# SAMC21N_Xplained_Pro_Target_MCU.net
KiCad netlist of a schematic drawn in Altium Designer
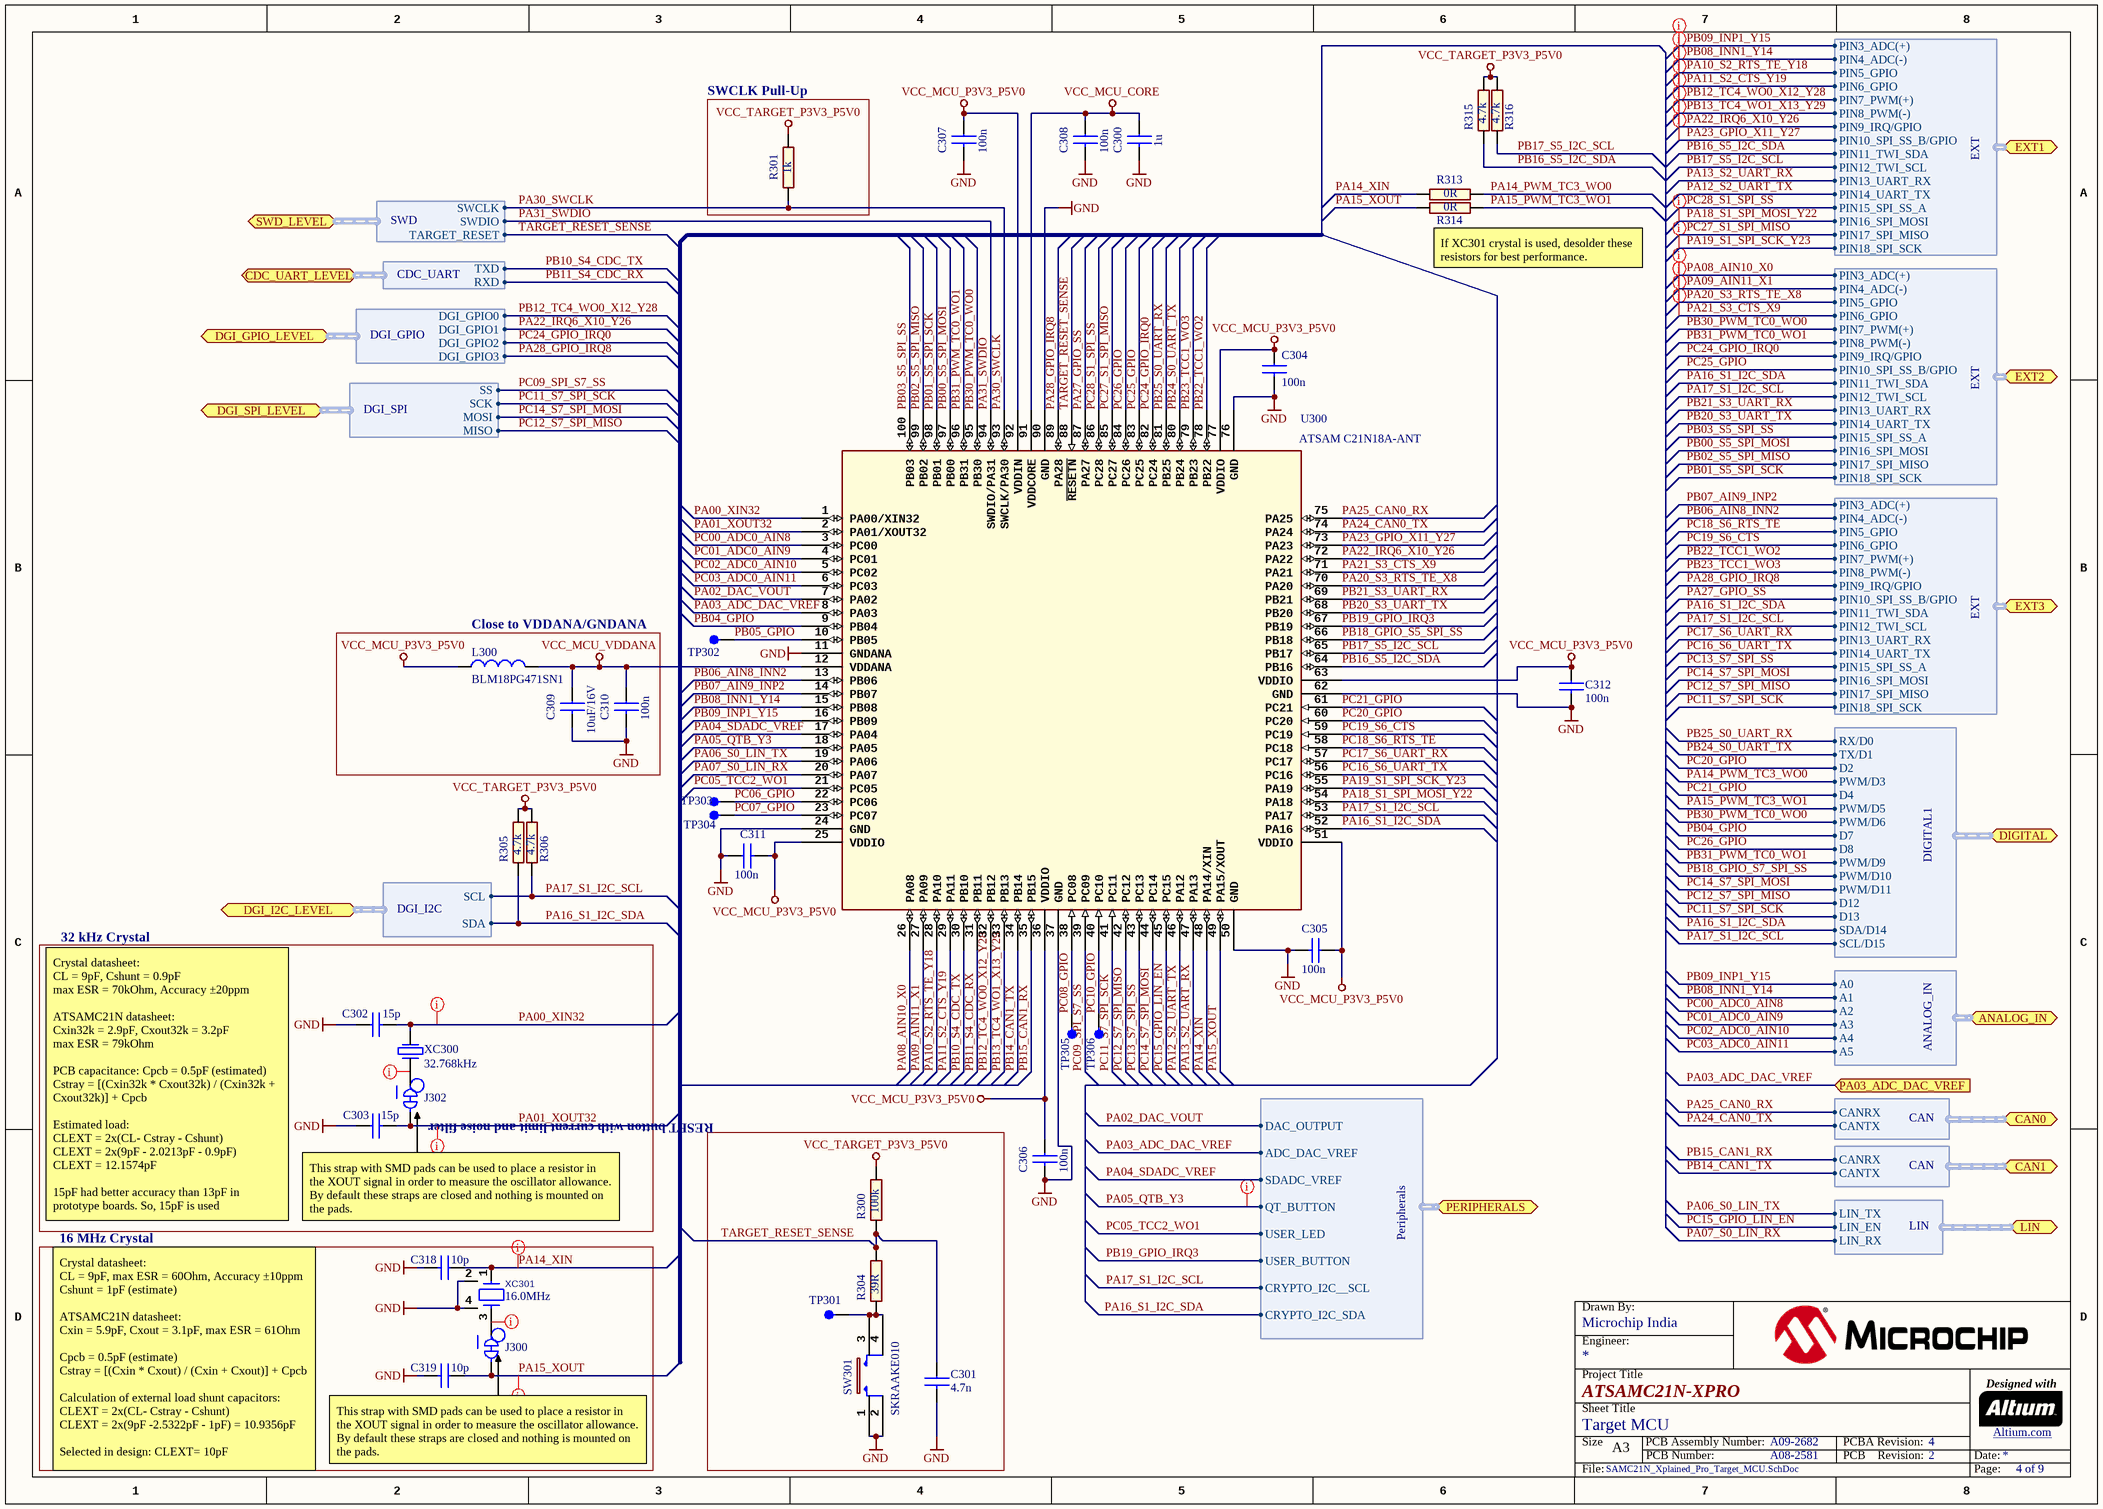
[diagram p0: SAMC21N_Xplained_Pro_Target_MCU.SchDoc]

(export (version "E")
  (design (tool "Eeschema 10.0.6"))
  (components
    (comp (ref "C300")
      (value "1u")
      (footprint "AP1-00001")
      (description "Ceramic capacitor, SMD 0402, X5R, 6.3V, +/-10% (de26942)")
      (fields
        (field (name "TOLERANCE") "+/-10%")
        (field (name "MANUFACTURER") "Kemet")
        (field (name "VERIFIED BY") "Lars Helge Mo")
      )
      (libsource (lib "AltiumDbLib") (part "CAP-NONPOL"))
    )
    (comp (ref "C301")
      (value "4.7n")
      (footprint "AP1-00001")
      (description "Ceramic capacitor, SMD 0402, X7R, 25V, +/-10% (de35287)")
      (fields
        (field (name "TOLERANCE") "25V, +/-10%")
        (field (name "Comment") "CAP-NONPOL")
        (field (name "VERIFIED BY") "Lars Helge Mo")
      )
      (libsource (lib "AltiumDbLib") (part "CAP-NONPOL"))
    )
    (comp (ref "C302")
      (value "15p")
      (footprint "AP1-00001")
      (description "Ceramic capacitor, SMD 0402, NP0, 50V, +/-5%")
      (fields
        (field (name "TOLERANCE") "50V, +/-5%")
        (field (name "MANUFACTURER") "AVX")
        (field (name "VERIFIED BY") "Lars Helge Mo")
      )
      (libsource (lib "AltiumDbLib") (part "CAP-NONPOL"))
    )
    (comp (ref "C303")
      (value "15p")
      (footprint "AP1-00001")
      (description "Ceramic capacitor, SMD 0402, NP0, 50V, +/-5%")
      (fields
        (field (name "TOLERANCE") "50V, +/-5%")
        (field (name "MANUFACTURER") "AVX")
        (field (name "VERIFIED BY") "Lars Helge Mo")
      )
      (libsource (lib "AltiumDbLib") (part "CAP-NONPOL"))
    )
    (comp (ref "C304")
      (value "100n")
      (footprint "AP1-00001")
      (description "Ceramic capacitor, SMD 0402, X7R, 16V, +/-10%")
      (fields
        (field (name "TOLERANCE") "16V, +/-10%")
        (field (name "MANUFACTURER") "Kemet")
        (field (name "VERIFIED BY") "Lars Helge Mo")
      )
      (libsource (lib "AltiumDbLib") (part "CAP-NONPOL"))
    )
    (comp (ref "C305")
      (value "100n")
      (footprint "AP1-00001")
      (description "Ceramic capacitor, SMD 0402, X7R, 16V, +/-10%")
      (fields
        (field (name "TOLERANCE") "16V, +/-10%")
        (field (name "MANUFACTURER") "Kemet")
        (field (name "VERIFIED BY") "Lars Helge Mo")
      )
      (libsource (lib "AltiumDbLib") (part "CAP-NONPOL"))
    )
    (comp (ref "C306")
      (value "100n")
      (footprint "AP1-00001")
      (description "Ceramic capacitor, SMD 0402, X7R, 16V, +/-10%")
      (fields
        (field (name "TOLERANCE") "16V, +/-10%")
        (field (name "MANUFACTURER") "Kemet")
        (field (name "VERIFIED BY") "Lars Helge Mo")
      )
      (libsource (lib "AltiumDbLib") (part "CAP-NONPOL"))
    )
    (comp (ref "C307")
      (value "100n")
      (footprint "AP1-00001")
      (description "Ceramic capacitor, SMD 0402, X7R, 16V, +/-10%")
      (fields
        (field (name "TOLERANCE") "16V, +/-10%")
        (field (name "MANUFACTURER") "Kemet")
        (field (name "VERIFIED BY") "Lars Helge Mo")
      )
      (libsource (lib "AltiumDbLib") (part "CAP-NONPOL"))
    )
    (comp (ref "C308")
      (value "100n")
      (footprint "AP1-00001")
      (description "Ceramic capacitor, SMD 0402, X7R, 16V, +/-10%")
      (fields
        (field (name "TOLERANCE") "16V, +/-10%")
        (field (name "MANUFACTURER") "Kemet")
        (field (name "VERIFIED BY") "Lars Helge Mo")
      )
      (libsource (lib "AltiumDbLib") (part "CAP-NONPOL"))
    )
    (comp (ref "C309")
      (value "10uF/16V")
      (footprint "AP1-00039")
      (description "Ceramic capacitor, SMD 0603, X5R, 16V, 10UF ± 20% (High Density)")
      (fields
        (field (name "MANUFACTURER") "Taiyo Yuden")
        (field (name "MPN") "EMK107BBJ106MA-T")
        (field (name "VERIFIED BY") "Lars Helge Mo")
      )
      (libsource (lib "AltiumDbLib") (part "CAP-NONPOL"))
    )
    (comp (ref "C310")
      (value "100n")
      (footprint "AP1-00001")
      (description "Ceramic capacitor, SMD 0402, X7R, 16V, +/-10%")
      (fields
        (field (name "TOLERANCE") "16V, +/-10%")
        (field (name "MANUFACTURER") "Kemet")
        (field (name "VERIFIED BY") "Lars Helge Mo")
      )
      (libsource (lib "AltiumDbLib") (part "CAP-NONPOL"))
    )
    (comp (ref "C311")
      (value "100n")
      (footprint "AP1-00001")
      (description "Ceramic capacitor, SMD 0402, X7R, 16V, +/-10%")
      (fields
        (field (name "TOLERANCE") "16V, +/-10%")
        (field (name "MANUFACTURER") "Kemet")
        (field (name "VERIFIED BY") "Lars Helge Mo")
      )
      (libsource (lib "AltiumDbLib") (part "CAP-NONPOL"))
    )
    (comp (ref "C312")
      (value "100n")
      (footprint "AP1-00001")
      (description "Ceramic capacitor, SMD 0402, X7R, 16V, +/-10%")
      (fields
        (field (name "TOLERANCE") "16V, +/-10%")
        (field (name "MANUFACTURER") "Kemet")
        (field (name "VERIFIED BY") "Lars Helge Mo")
      )
      (libsource (lib "AltiumDbLib") (part "CAP-NONPOL"))
    )
    (comp (ref "C318")
      (value "10p")
      (footprint "AP1-00001")
      (description "Ceramic capacitor, SMD 0402, NP0, 50V, +/-5%")
      (fields
        (field (name "TOLERANCE") "50V, +/-5%")
        (field (name "Comment") "CAP-NONPOL")
        (field (name "VERIFIED BY") "Lars Helge Mo")
      )
      (libsource (lib "AltiumDbLib") (part "CAP-NONPOL"))
    )
    (comp (ref "C319")
      (value "10p")
      (footprint "AP1-00001")
      (description "Ceramic capacitor, SMD 0402, NP0, 50V, +/-5%")
      (fields
        (field (name "TOLERANCE") "50V, +/-5%")
        (field (name "Comment") "CAP-NONPOL")
        (field (name "VERIFIED BY") "Lars Helge Mo")
      )
      (libsource (lib "AltiumDbLib") (part "CAP-NONPOL"))
    )
    (comp (ref "J300")
      (value "~")
      (footprint "AP9-00044")
      (description "Default closed SMD strap, 0603 size")
      (libsource (lib "AltiumDbLib") (part "SMD-STRAP_CLOSED"))
    )
    (comp (ref "J302")
      (value "~")
      (footprint "AP9-00044")
      (description "Default closed SMD strap, 0603 size")
      (libsource (lib "AltiumDbLib") (part "SMD-STRAP_CLOSED"))
    )
    (comp (ref "L300")
      (value "BLM18PG471SN1")
      (footprint "AP3-00005")
      (description "SMD RF inductor 0603. Z=470Ohm (@100MHz), Max R(dc)=0.65Ohm, Max current=1A")
      (fields
        (field (name "TOLERANCE") "±25%")
        (field (name "MANUFACTURER") "Murata")
        (field (name "VERIFIED BY") "Lars Helge Mo")
      )
      (libsource (lib "AltiumDbLib") (part "INDUCTOR"))
    )
    (comp (ref "R300")
      (value "100k")
      (footprint "AP2-00011")
      (description "Thick film resistor, SMD 0402, 1/16W, 1%")
      (fields
        (field (name "TOLERANCE") "1 %")
        (field (name "Comment") "R2")
        (field (name "VERIFIED BY") "Lars Helge Mo")
      )
      (libsource (lib "AltiumDbLib") (part "R2"))
    )
    (comp (ref "R301")
      (value "1k")
      (footprint "AP2-00000")
      (description "Thick film resistor, SMD 0402, 1/16W, 1%")
      (fields
        (field (name "TOLERANCE") "1 %")
        (field (name "Comment") "R2")
        (field (name "VERIFIED BY") "Lars Helge Mo")
      )
      (libsource (lib "AltiumDbLib") (part "R2"))
    )
    (comp (ref "R304")
      (value "39R")
      (footprint "AP2-00011")
      (description "Thick film resistor, SMD 0402, 1/16W, 1%")
      (fields
        (field (name "TOLERANCE") "1 %")
        (field (name "Comment") "R2")
        (field (name "VERIFIED BY") "Lars Helge Mo")
      )
      (libsource (lib "") (part "R2_2"))
    )
    (comp (ref "R305")
      (value "4.7k")
      (footprint "AP2-00000")
      (description "Thick film resistor, SMD 0402, 1/16W, 1%")
      (fields
        (field (name "TOLERANCE") "1 %")
        (field (name "Comment") "R2")
        (field (name "VERIFIED BY") "Lars Helge Mo")
      )
      (libsource (lib "AltiumDbLib") (part "R2"))
    )
    (comp (ref "R306")
      (value "4.7k")
      (footprint "AP2-00000")
      (description "Thick film resistor, SMD 0402, 1/16W, 1%")
      (fields
        (field (name "TOLERANCE") "1 %")
        (field (name "Comment") "R2")
        (field (name "VERIFIED BY") "Lars Helge Mo")
      )
      (libsource (lib "AltiumDbLib") (part "R2"))
    )
    (comp (ref "R313")
      (value "0R")
      (footprint "AP2-00000")
      (description "Thick film resistor, SMD 0402, 1/16W, 1%")
      (fields
        (field (name "TOLERANCE") "1 %")
        (field (name "Comment") "R2")
        (field (name "VERIFIED BY") "Lars Helge Mo")
      )
      (libsource (lib "") (part "R2_1"))
    )
    (comp (ref "R314")
      (value "0R")
      (footprint "AP2-00000")
      (description "Thick film resistor, SMD 0402, 1/16W, 1%")
      (fields
        (field (name "TOLERANCE") "1 %")
        (field (name "Comment") "R2")
        (field (name "VERIFIED BY") "Lars Helge Mo")
      )
      (libsource (lib "") (part "R2_1"))
    )
    (comp (ref "R315")
      (value "4.7k")
      (footprint "AP2-00000")
      (description "Thick film resistor, SMD 0402, 1/16W, 1%")
      (fields
        (field (name "TOLERANCE") "1 %")
        (field (name "Comment") "R2")
        (field (name "VERIFIED BY") "Lars Helge Mo")
      )
      (libsource (lib "AltiumDbLib") (part "R2"))
    )
    (comp (ref "R316")
      (value "4.7k")
      (footprint "AP2-00000")
      (description "Thick film resistor, SMD 0402, 1/16W, 1%")
      (fields
        (field (name "TOLERANCE") "1 %")
        (field (name "Comment") "R2")
        (field (name "VERIFIED BY") "Lars Helge Mo")
      )
      (libsource (lib "AltiumDbLib") (part "R2"))
    )
    (comp (ref "SW301")
      (value "SKRAAKE010")
      (footprint "AP8-00137")
      (description "6.2x6.2 mm SMD tact switch, same as A08-0091 but less force is needed")
      (fields
        (field (name "MANUFACTURER") "ALPS")
        (field (name "Comment") "Can be ordered in low volumes from Mouser")
        (field (name "VERIFIED BY") "Ketil Skjerve")
      )
      (libsource (lib "AltiumDbLib") (part "PUSHBUTTON1"))
    )
    (comp (ref "TP301")
      (value "TESTPOINT")
      (footprint "AP8-00010")
      (description "Single SMD testpad")
      (fields (field (name "VERIFIED BY") "Sveinung Helgeland"))
      (libsource (lib "AltiumDbLib") (part "TESTPOINT"))
    )
    (comp (ref "TP302")
      (value "TESTPOINT")
      (footprint "AP8-00256")
      (description "Hole for user grid with 1.27 mm pitch, 1x1 mm pad")
      (fields (field (name "VERIFIED BY") "Sveinung Helgeland"))
      (libsource (lib "AltiumDbLib") (part "TESTPOINT"))
    )
    (comp (ref "TP303")
      (value "TESTPOINT")
      (footprint "AP8-00256")
      (description "Hole for user grid with 1.27 mm pitch, 1x1 mm pad")
      (fields (field (name "VERIFIED BY") "Sveinung Helgeland"))
      (libsource (lib "AltiumDbLib") (part "TESTPOINT"))
    )
    (comp (ref "TP304")
      (value "TESTPOINT")
      (footprint "AP8-00256")
      (description "Hole for user grid with 1.27 mm pitch, 1x1 mm pad")
      (fields (field (name "VERIFIED BY") "Sveinung Helgeland"))
      (libsource (lib "AltiumDbLib") (part "TESTPOINT"))
    )
    (comp (ref "TP305")
      (value "TESTPOINT")
      (footprint "AP8-00256")
      (description "Hole for user grid with 1.27 mm pitch, 1x1 mm pad")
      (fields (field (name "VERIFIED BY") "Sveinung Helgeland"))
      (libsource (lib "AltiumDbLib") (part "TESTPOINT"))
    )
    (comp (ref "TP306")
      (value "TESTPOINT")
      (footprint "AP8-00256")
      (description "Hole for user grid with 1.27 mm pitch, 1x1 mm pad")
      (fields (field (name "VERIFIED BY") "Sveinung Helgeland"))
      (libsource (lib "AltiumDbLib") (part "TESTPOINT"))
    )
    (comp (ref "U300")
      (value "ATSAM C21N18A-ANT")
      (footprint "AP6-00008")
      (description "Atmel 32-bit ARM Cortex-M0+ processor 100pin 256KB Flash 32KB SRAM 48MHz freq")
      (fields (field (name "MANUFACTURER") "ATMEL") (field (name "Comment") "SAMC21N_TQFP100"))
      (libsource (lib "AltiumDbLib") (part "SAMC21N_TQFP100"))
    )
    (comp (ref "XC300")
      (value "32.768kHz")
      (footprint "AP7-00090")
      (description "Kyocera ST3215SB32768E0HPWBB, 32.768kHz, 9pF, SMD tuning fork crystal")
      (fields
        (field (name "TOLERANCE") "Â±20ppm")
        (field (name "MANUFACTURER") "Kyocera Crystal Device Corporation")
        (field (name "VERIFIED BY") "Sveinung Helgeland")
      )
      (libsource (lib "AltiumDbLib") (part "CRYSTAL"))
    )
    (comp (ref "XC301")
      (value "16.0MHz")
      (footprint "AP7-00061")
      (description "16MHz uXtal, 3.2 x 2.5 mm SMD, CL=9pF, 15PPM, ESR=80ohm(Max.")
      (fields (field (name "TOLERANCE") "15ppm") (field (name "MANUFACTURER") "Epson Toyocom"))
      (libsource (lib "AltiumDbLib") (part "TSX-3225"))
    )
  )
  (nets
    (net (code "12") (name "/PA00_XIN32") (class "Default")
      (node (ref "C302") (pin "2") (pinfunction "2_2") (pintype "passive"))
      (node (ref "U300") (pin "1") (pinfunction "PA00/XIN32_1") (pintype "bidirectional"))
      (node (ref "XC300") (pin "1") (pinfunction "1_1") (pintype "passive"))
    )
    (net (code "13") (name "/PA01_XOUT32") (class "Default")
      (node (ref "C303") (pin "2") (pinfunction "2_2") (pintype "passive"))
      (node (ref "J302") (pin "2") (pinfunction "2_2") (pintype "passive"))
      (node (ref "U300") (pin "2") (pinfunction "PA01/XOUT32_2") (pintype "bidirectional"))
    )
    (net (code "14") (name "/PA02_DAC_VOUT") (class "Default")
      (node (ref "U300") (pin "7") (pinfunction "PA02_7") (pintype "bidirectional"))
    )
    (net (code "15") (name "/PA03_ADC_DAC_VREF") (class "Default")
      (node (ref "U300") (pin "8") (pinfunction "PA03_8") (pintype "bidirectional"))
    )
    (net (code "16") (name "/PA04_SDADC_VREF") (class "Default")
      (node (ref "U300") (pin "17") (pinfunction "PA04_17") (pintype "bidirectional"))
    )
    (net (code "17") (name "/PA05_QTB_Y3") (class "Default")
      (node (ref "U300") (pin "18") (pinfunction "PA05_18") (pintype "bidirectional"))
    )
    (net (code "18") (name "/PA06_S0_LIN_TX") (class "Default")
      (node (ref "U300") (pin "19") (pinfunction "PA06_19") (pintype "bidirectional"))
    )
    (net (code "19") (name "/PA07_S0_LIN_RX") (class "Default")
      (node (ref "U300") (pin "20") (pinfunction "PA07_20") (pintype "bidirectional"))
    )
    (net (code "20") (name "/PA08_AIN10_X0") (class "Default")
      (node (ref "U300") (pin "26") (pinfunction "PA08_26") (pintype "bidirectional"))
    )
    (net (code "21") (name "/PA09_AIN11_X1") (class "Default")
      (node (ref "U300") (pin "27") (pinfunction "PA09_27") (pintype "bidirectional"))
    )
    (net (code "22") (name "/PA10_S2_RTS_TE_Y18") (class "Default")
      (node (ref "U300") (pin "28") (pinfunction "PA10_28") (pintype "bidirectional"))
    )
    (net (code "23") (name "/PA11_S2_CTS_Y19") (class "Default")
      (node (ref "U300") (pin "29") (pinfunction "PA11_29") (pintype "bidirectional"))
    )
    (net (code "24") (name "/PA12_S2_UART_TX") (class "Default")
      (node (ref "U300") (pin "46") (pinfunction "PA12_46") (pintype "bidirectional"))
    )
    (net (code "25") (name "/PA13_S2_UART_RX") (class "Default")
      (node (ref "U300") (pin "47") (pinfunction "PA13_47") (pintype "bidirectional"))
    )
    (net (code "26") (name "/PA14_PWM_TC3_WO0") (class "Default")
      (node (ref "R313") (pin "2") (pinfunction "2_2") (pintype "passive"))
    )
    (net (code "27") (name "/PA14_XIN") (class "Default")
      (node (ref "C318") (pin "1") (pinfunction "1_1") (pintype "passive"))
      (node (ref "R313") (pin "1") (pinfunction "1_1") (pintype "passive"))
      (node (ref "U300") (pin "48") (pinfunction "PA14/XIN_48") (pintype "bidirectional"))
      (node (ref "XC301") (pin "1") (pinfunction "IN_1") (pintype "passive"))
    )
    (net (code "28") (name "/PA15_PWM_TC3_WO1") (class "Default")
      (node (ref "R314") (pin "2") (pinfunction "2_2") (pintype "passive"))
    )
    (net (code "29") (name "/PA15_XOUT") (class "Default")
      (node (ref "C319") (pin "1") (pinfunction "1_1") (pintype "passive"))
      (node (ref "J300") (pin "2") (pinfunction "2_2") (pintype "passive"))
      (node (ref "R314") (pin "1") (pinfunction "1_1") (pintype "passive"))
      (node (ref "U300") (pin "49") (pinfunction "PA15/XOUT_49") (pintype "bidirectional"))
    )
    (net (code "30") (name "/PA16_S1_I2C_SDA") (class "Default")
      (node (ref "R305") (pin "1") (pinfunction "1_1") (pintype "passive"))
      (node (ref "U300") (pin "52") (pinfunction "PA16_52") (pintype "bidirectional"))
    )
    (net (code "31") (name "/PA17_S1_I2C_SCL") (class "Default")
      (node (ref "R306") (pin "1") (pinfunction "1_1") (pintype "passive"))
      (node (ref "U300") (pin "53") (pinfunction "PA17_53") (pintype "bidirectional"))
    )
    (net (code "32") (name "/PA18_S1_SPI_MOSI_Y22") (class "Default")
      (node (ref "U300") (pin "54") (pinfunction "PA18_54") (pintype "bidirectional"))
    )
    (net (code "33") (name "/PA19_S1_SPI_SCK_Y23") (class "Default")
      (node (ref "U300") (pin "55") (pinfunction "PA19_55") (pintype "bidirectional"))
    )
    (net (code "34") (name "/PA20_S3_RTS_TE_X8") (class "Default")
      (node (ref "U300") (pin "70") (pinfunction "PA20_70") (pintype "bidirectional"))
    )
    (net (code "35") (name "/PA21_S3_CTS_X9") (class "Default")
      (node (ref "U300") (pin "71") (pinfunction "PA21_71") (pintype "bidirectional"))
    )
    (net (code "36") (name "/PA22_IRQ6_X10_Y26") (class "Default")
      (node (ref "U300") (pin "72") (pinfunction "PA22_72") (pintype "bidirectional"))
    )
    (net (code "37") (name "/PA23_GPIO_X11_Y27") (class "Default")
      (node (ref "U300") (pin "73") (pinfunction "PA23_73") (pintype "bidirectional"))
    )
    (net (code "38") (name "/PA24_CAN0_TX") (class "Default")
      (node (ref "U300") (pin "74") (pinfunction "PA24_74") (pintype "bidirectional"))
    )
    (net (code "39") (name "/PA25_CAN0_RX") (class "Default")
      (node (ref "U300") (pin "75") (pinfunction "PA25_75") (pintype "bidirectional"))
    )
    (net (code "40") (name "/PA27_GPIO_SS") (class "Default")
      (node (ref "U300") (pin "87") (pinfunction "PA27_87") (pintype "bidirectional"))
    )
    (net (code "41") (name "/PA28_GPIO_IRQ8") (class "Default")
      (node (ref "U300") (pin "89") (pinfunction "PA28_89") (pintype "bidirectional"))
    )
    (net (code "42") (name "/PA30_SWCLK") (class "Default")
      (node (ref "R301") (pin "1") (pinfunction "1_1") (pintype "passive"))
      (node (ref "U300") (pin "93") (pinfunction "SWCLK/PA30_93") (pintype "bidirectional"))
    )
    (net (code "43") (name "/PA31_SWDIO") (class "Default")
      (node (ref "U300") (pin "94") (pinfunction "SWDIO/PA31_94") (pintype "bidirectional"))
    )
    (net (code "44") (name "/PB00_S5_SPI_MOSI") (class "Default")
      (node (ref "U300") (pin "97") (pinfunction "PB00_97") (pintype "bidirectional"))
    )
    (net (code "45") (name "/PB01_S5_SPI_SCK") (class "Default")
      (node (ref "U300") (pin "98") (pinfunction "PB01_98") (pintype "bidirectional"))
    )
    (net (code "46") (name "/PB02_S5_SPI_MISO") (class "Default")
      (node (ref "U300") (pin "99") (pinfunction "PB02_99") (pintype "bidirectional"))
    )
    (net (code "47") (name "/PB03_S5_SPI_SS") (class "Default")
      (node (ref "U300") (pin "100") (pinfunction "PB03_100") (pintype "bidirectional"))
    )
    (net (code "48") (name "/PB04_GPIO") (class "Default")
      (node (ref "U300") (pin "9") (pinfunction "PB04_9") (pintype "bidirectional"))
    )
    (net (code "49") (name "/PB05_GPIO") (class "Default")
      (node (ref "TP302") (pin "1") (pinfunction "1_1") (pintype "passive"))
      (node (ref "U300") (pin "10") (pinfunction "PB05_10") (pintype "bidirectional"))
    )
    (net (code "50") (name "/PB06_AIN8_INN2") (class "Default")
      (node (ref "U300") (pin "13") (pinfunction "PB06_13") (pintype "bidirectional"))
    )
    (net (code "51") (name "/PB07_AIN9_INP2") (class "Default")
      (node (ref "U300") (pin "14") (pinfunction "PB07_14") (pintype "bidirectional"))
    )
    (net (code "52") (name "/PB08_INN1_Y14") (class "Default")
      (node (ref "U300") (pin "15") (pinfunction "PB08_15") (pintype "bidirectional"))
    )
    (net (code "53") (name "/PB09_INP1_Y15") (class "Default")
      (node (ref "U300") (pin "16") (pinfunction "PB09_16") (pintype "bidirectional"))
    )
    (net (code "54") (name "/PB10_S4_CDC_TX") (class "Default")
      (node (ref "U300") (pin "30") (pinfunction "PB10_30") (pintype "bidirectional"))
    )
    (net (code "55") (name "/PB11_S4_CDC_RX") (class "Default")
      (node (ref "U300") (pin "31") (pinfunction "PB11_31") (pintype "bidirectional"))
    )
    (net (code "56") (name "/PB12_TC4_WO0_X12_Y28") (class "Default")
      (node (ref "U300") (pin "32") (pinfunction "PB12_32") (pintype "bidirectional"))
    )
    (net (code "57") (name "/PB13_TC4_WO1_X13_Y29") (class "Default")
      (node (ref "U300") (pin "33") (pinfunction "PB13_33") (pintype "bidirectional"))
    )
    (net (code "58") (name "/PB14_CAN1_TX") (class "Default")
      (node (ref "U300") (pin "34") (pinfunction "PB14_34") (pintype "bidirectional"))
    )
    (net (code "59") (name "/PB15_CAN1_RX") (class "Default")
      (node (ref "U300") (pin "35") (pinfunction "PB15_35") (pintype "bidirectional"))
    )
    (net (code "60") (name "/PB16_S5_I2C_SDA") (class "Default")
      (node (ref "R315") (pin "1") (pinfunction "1_1") (pintype "passive"))
      (node (ref "U300") (pin "64") (pinfunction "PB16_64") (pintype "bidirectional"))
    )
    (net (code "61") (name "/PB17_S5_I2C_SCL") (class "Default")
      (node (ref "R316") (pin "1") (pinfunction "1_1") (pintype "passive"))
      (node (ref "U300") (pin "65") (pinfunction "PB17_65") (pintype "bidirectional"))
    )
    (net (code "62") (name "/PB18_GPIO_S5_SPI_SS") (class "Default")
      (node (ref "U300") (pin "66") (pinfunction "PB18_66") (pintype "bidirectional"))
    )
    (net (code "64") (name "/PB19_GPIO_IRQ3") (class "Default")
      (node (ref "U300") (pin "67") (pinfunction "PB19_67") (pintype "bidirectional"))
    )
    (net (code "65") (name "/PB20_S3_UART_TX") (class "Default")
      (node (ref "U300") (pin "68") (pinfunction "PB20_68") (pintype "bidirectional"))
    )
    (net (code "66") (name "/PB21_S3_UART_RX") (class "Default")
      (node (ref "U300") (pin "69") (pinfunction "PB21_69") (pintype "bidirectional"))
    )
    (net (code "67") (name "/PB22_TCC1_WO2") (class "Default")
      (node (ref "U300") (pin "78") (pinfunction "PB22_78") (pintype "bidirectional"))
    )
    (net (code "68") (name "/PB23_TCC1_WO3") (class "Default")
      (node (ref "U300") (pin "79") (pinfunction "PB23_79") (pintype "bidirectional"))
    )
    (net (code "69") (name "/PB24_S0_UART_TX") (class "Default")
      (node (ref "U300") (pin "80") (pinfunction "PB24_80") (pintype "bidirectional"))
    )
    (net (code "70") (name "/PB25_S0_UART_RX") (class "Default")
      (node (ref "U300") (pin "81") (pinfunction "PB25_81") (pintype "bidirectional"))
    )
    (net (code "71") (name "/PB30_PWM_TC0_WO0") (class "Default")
      (node (ref "U300") (pin "95") (pinfunction "PB30_95") (pintype "bidirectional"))
    )
    (net (code "72") (name "/PB31_PWM_TC0_WO1") (class "Default")
      (node (ref "U300") (pin "96") (pinfunction "PB31_96") (pintype "bidirectional"))
    )
    (net (code "73") (name "/PC00_ADC0_AIN8") (class "Default")
      (node (ref "U300") (pin "3") (pinfunction "PC00_3") (pintype "bidirectional"))
    )
    (net (code "74") (name "/PC01_ADC0_AIN9") (class "Default")
      (node (ref "U300") (pin "4") (pinfunction "PC01_4") (pintype "bidirectional"))
    )
    (net (code "75") (name "/PC02_ADC0_AIN10") (class "Default")
      (node (ref "U300") (pin "5") (pinfunction "PC02_5") (pintype "bidirectional"))
    )
    (net (code "76") (name "/PC03_ADC0_AIN11") (class "Default")
      (node (ref "U300") (pin "6") (pinfunction "PC03_6") (pintype "bidirectional"))
    )
    (net (code "77") (name "/PC05_TCC2_WO1") (class "Default")
      (node (ref "U300") (pin "21") (pinfunction "PC05_21") (pintype "bidirectional"))
    )
    (net (code "78") (name "/PC06_GPIO") (class "Default")
      (node (ref "TP303") (pin "1") (pinfunction "1_1") (pintype "passive"))
      (node (ref "U300") (pin "22") (pinfunction "PC06_22") (pintype "bidirectional"))
    )
    (net (code "79") (name "/PC07_GPIO") (class "Default")
      (node (ref "TP304") (pin "1") (pinfunction "1_1") (pintype "passive"))
      (node (ref "U300") (pin "23") (pinfunction "PC07_23") (pintype "bidirectional"))
    )
    (net (code "80") (name "/PC08_GPIO") (class "Default")
      (node (ref "TP305") (pin "1") (pinfunction "1_1") (pintype "passive"))
      (node (ref "U300") (pin "38") (pinfunction "PC08_38") (pintype "input"))
    )
    (net (code "81") (name "/PC09_SPI_S7_SS") (class "Default")
      (node (ref "U300") (pin "39") (pinfunction "PC09_39") (pintype "input"))
    )
    (net (code "82") (name "/PC10_GPIO") (class "Default")
      (node (ref "TP306") (pin "1") (pinfunction "1_1") (pintype "passive"))
      (node (ref "U300") (pin "40") (pinfunction "PC10_40") (pintype "input"))
    )
    (net (code "83") (name "/PC11_S7_SPI_SCK") (class "Default")
      (node (ref "U300") (pin "41") (pinfunction "PC11_41") (pintype "input"))
    )
    (net (code "84") (name "/PC12_S7_SPI_MISO") (class "Default")
      (node (ref "U300") (pin "42") (pinfunction "PC12_42") (pintype "bidirectional"))
    )
    (net (code "85") (name "/PC13_S7_SPI_SS") (class "Default")
      (node (ref "U300") (pin "43") (pinfunction "PC13_43") (pintype "bidirectional"))
    )
    (net (code "86") (name "/PC14_S7_SPI_MOSI") (class "Default")
      (node (ref "U300") (pin "44") (pinfunction "PC14_44") (pintype "bidirectional"))
    )
    (net (code "87") (name "/PC15_GPIO_LIN_EN") (class "Default")
      (node (ref "U300") (pin "45") (pinfunction "PC15_45") (pintype "bidirectional"))
    )
    (net (code "88") (name "/PC16_S6_UART_TX") (class "Default")
      (node (ref "U300") (pin "56") (pinfunction "PC16_56") (pintype "bidirectional"))
    )
    (net (code "89") (name "/PC17_S6_UART_RX") (class "Default")
      (node (ref "U300") (pin "57") (pinfunction "PC17_57") (pintype "bidirectional"))
    )
    (net (code "90") (name "/PC18_S6_RTS_TE") (class "Default")
      (node (ref "U300") (pin "58") (pinfunction "PC18_58") (pintype "input"))
    )
    (net (code "91") (name "/PC19_S6_CTS") (class "Default")
      (node (ref "U300") (pin "59") (pinfunction "PC19_59") (pintype "input"))
    )
    (net (code "92") (name "/PC20_GPIO") (class "Default")
      (node (ref "U300") (pin "60") (pinfunction "PC20_60") (pintype "input"))
    )
    (net (code "93") (name "/PC21_GPIO") (class "Default")
      (node (ref "U300") (pin "61") (pinfunction "PC21_61") (pintype "input"))
    )
    (net (code "94") (name "/PC24_GPIO_IRQ0") (class "Default")
      (node (ref "U300") (pin "82") (pinfunction "PC24_82") (pintype "bidirectional"))
    )
    (net (code "95") (name "/PC25_GPIO") (class "Default")
      (node (ref "U300") (pin "83") (pinfunction "PC25_83") (pintype "bidirectional"))
    )
    (net (code "96") (name "/PC26_GPIO") (class "Default")
      (node (ref "U300") (pin "84") (pinfunction "PC26_84") (pintype "bidirectional"))
    )
    (net (code "97") (name "/PC27_S1_SPI_MISO") (class "Default")
      (node (ref "U300") (pin "85") (pinfunction "PC27_85") (pintype "bidirectional"))
    )
    (net (code "98") (name "/PC28_S1_SPI_SS") (class "Default")
      (node (ref "U300") (pin "86") (pinfunction "PC28_86") (pintype "bidirectional"))
    )
    (net (code "99") (name "/TARGET_RESET_SENSE") (class "Default")
      (node (ref "C301") (pin "1") (pinfunction "1_1") (pintype "passive"))
      (node (ref "R300") (pin "1") (pinfunction "1_1") (pintype "passive"))
      (node (ref "R304") (pin "2") (pinfunction "2_2") (pintype "passive"))
      (node (ref "U300") (pin "88") (pinfunction "~{RESETN}_88") (pintype "input"))
    )
    (net (code "111") (name "GND") (class "Default")
      (node (ref "C300") (pin "2") (pinfunction "2_2") (pintype "passive"))
      (node (ref "C301") (pin "2") (pinfunction "2_2") (pintype "passive"))
      (node (ref "C302") (pin "1") (pinfunction "1_1") (pintype "passive"))
      (node (ref "C303") (pin "1") (pinfunction "1_1") (pintype "passive"))
      (node (ref "C304") (pin "2") (pinfunction "2_2") (pintype "passive"))
      (node (ref "C305") (pin "2") (pinfunction "2_2") (pintype "passive"))
      (node (ref "C306") (pin "2") (pinfunction "2_2") (pintype "passive"))
      (node (ref "C307") (pin "2") (pinfunction "2_2") (pintype "passive"))
      (node (ref "C308") (pin "2") (pinfunction "2_2") (pintype "passive"))
      (node (ref "C309") (pin "2") (pinfunction "2_2") (pintype "passive"))
      (node (ref "C310") (pin "2") (pinfunction "2_2") (pintype "passive"))
      (node (ref "C311") (pin "1") (pinfunction "1_1") (pintype "passive"))
      (node (ref "C312") (pin "2") (pinfunction "2_2") (pintype "passive"))
      (node (ref "C318") (pin "2") (pinfunction "2_2") (pintype "passive"))
      (node (ref "C319") (pin "2") (pinfunction "2_2") (pintype "passive"))
      (node (ref "SW301") (pin "1") (pinfunction "1_1") (pintype "passive"))
      (node (ref "SW301") (pin "2") (pinfunction "2_2") (pintype "passive"))
      (node (ref "U300") (pin "11") (pinfunction "GNDANA_11") (pintype "power_in"))
      (node (ref "U300") (pin "24") (pinfunction "GND_24") (pintype "power_in"))
      (node (ref "U300") (pin "37") (pinfunction "GND_37") (pintype "power_in"))
      (node (ref "U300") (pin "50") (pinfunction "GND_50") (pintype "power_in"))
      (node (ref "U300") (pin "62") (pinfunction "GND_62") (pintype "power_in"))
      (node (ref "U300") (pin "76") (pinfunction "GND_76") (pintype "power_in"))
      (node (ref "U300") (pin "90") (pinfunction "GND_90") (pintype "power_in"))
      (node (ref "XC301") (pin "2") (pinfunction "GND_2") (pintype "passive"))
      (node (ref "XC301") (pin "4") (pinfunction "GND_4") (pintype "passive"))
    )
    (net (code "112") (name "Net-(J302-Pad1)") (class "Default")
      (node (ref "J302") (pin "1") (pinfunction "1_1") (pintype "passive"))
      (node (ref "XC300") (pin "2") (pinfunction "2_2") (pintype "passive"))
    )
    (net (code "113") (name "Net-(R304-Pad1)") (class "Default")
      (node (ref "R304") (pin "1") (pinfunction "1_1") (pintype "passive"))
      (node (ref "SW301") (pin "3") (pinfunction "3_3") (pintype "passive"))
      (node (ref "SW301") (pin "4") (pinfunction "4_4") (pintype "passive"))
      (node (ref "TP301") (pin "1") (pinfunction "1_1") (pintype "passive"))
    )
    (net (code "114") (name "Net-(XC301-OUT)") (class "Default")
      (node (ref "J300") (pin "1") (pinfunction "1_1") (pintype "passive"))
      (node (ref "XC301") (pin "3") (pinfunction "OUT_3") (pintype "passive"))
    )
    (net (code "115") (name "VCC_MCU_CORE") (class "Default")
      (node (ref "C300") (pin "1") (pinfunction "1_1") (pintype "passive"))
      (node (ref "C308") (pin "1") (pinfunction "1_1") (pintype "passive"))
      (node (ref "U300") (pin "91") (pinfunction "VDDCORE_91") (pintype "power_in"))
    )
    (net (code "116") (name "VCC_MCU_P3V3_P5V0") (class "Default")
      (node (ref "C304") (pin "1") (pinfunction "1_1") (pintype "passive"))
      (node (ref "C305") (pin "1") (pinfunction "1_1") (pintype "passive"))
      (node (ref "C306") (pin "1") (pinfunction "1_1") (pintype "passive"))
      (node (ref "C307") (pin "1") (pinfunction "1_1") (pintype "passive"))
      (node (ref "C311") (pin "2") (pinfunction "2_2") (pintype "passive"))
      (node (ref "C312") (pin "1") (pinfunction "1_1") (pintype "passive"))
      (node (ref "L300") (pin "1") (pinfunction "1_1") (pintype "passive"))
      (node (ref "U300") (pin "25") (pinfunction "VDDIO_25") (pintype "power_in"))
      (node (ref "U300") (pin "36") (pinfunction "VDDIO_36") (pintype "power_in"))
      (node (ref "U300") (pin "51") (pinfunction "VDDIO_51") (pintype "power_in"))
      (node (ref "U300") (pin "63") (pinfunction "VDDIO_63") (pintype "power_in"))
      (node (ref "U300") (pin "77") (pinfunction "VDDIO_77") (pintype "power_in"))
      (node (ref "U300") (pin "92") (pinfunction "VDDIN_92") (pintype "power_in"))
    )
    (net (code "117") (name "VCC_MCU_VDDANA") (class "Default")
      (node (ref "C309") (pin "1") (pinfunction "1_1") (pintype "passive"))
      (node (ref "C310") (pin "1") (pinfunction "1_1") (pintype "passive"))
      (node (ref "L300") (pin "2") (pinfunction "2_2") (pintype "passive"))
      (node (ref "U300") (pin "12") (pinfunction "VDDANA_12") (pintype "power_in"))
    )
    (net (code "118") (name "VCC_TARGET_P3V3_P5V0") (class "Default")
      (node (ref "R300") (pin "2") (pinfunction "2_2") (pintype "passive"))
      (node (ref "R301") (pin "2") (pinfunction "2_2") (pintype "passive"))
      (node (ref "R305") (pin "2") (pinfunction "2_2") (pintype "passive"))
      (node (ref "R306") (pin "2") (pinfunction "2_2") (pintype "passive"))
      (node (ref "R315") (pin "2") (pinfunction "2_2") (pintype "passive"))
      (node (ref "R316") (pin "2") (pinfunction "2_2") (pintype "passive"))
    )
  )
)
